# Power.net
KiCad netlist of a schematic drawn in Altium Designer
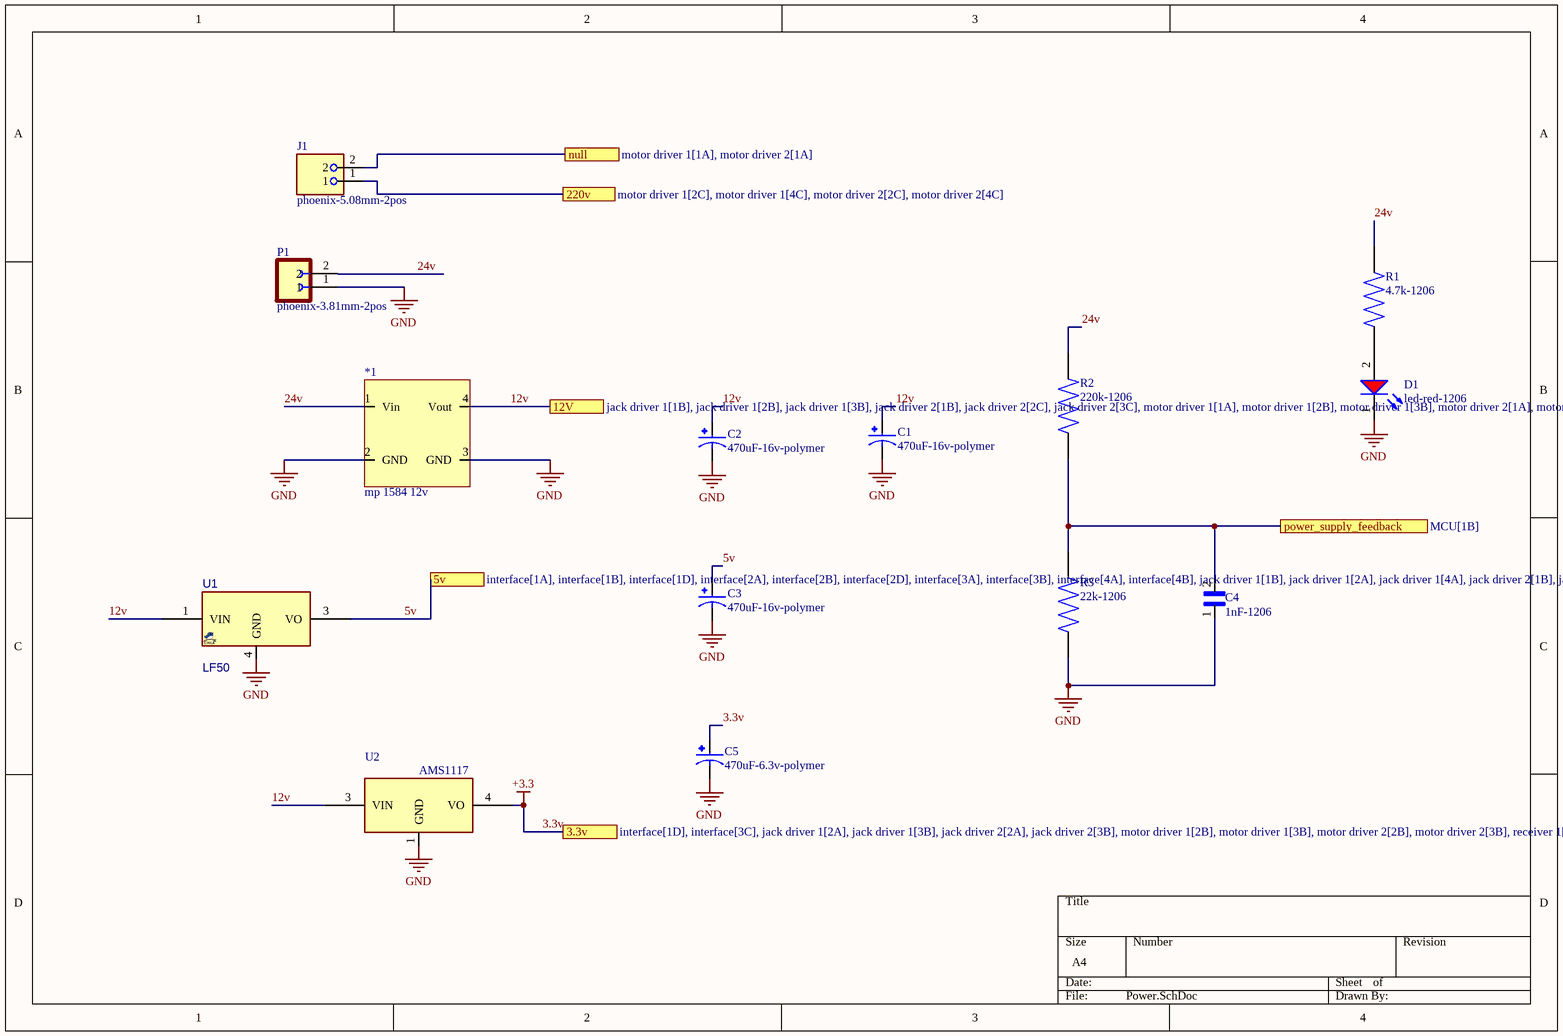
[diagram p0: Power.SchDoc]

(export (version "E")
  (design (tool "Eeschema 10.0.6"))
  (components
    (comp (ref "*1")
      (value "mp 1584 12v")
      (footprint "PCBComponent_1")
      (libsource (lib "mp1584 module") (part "Component_1"))
    )
    (comp (ref "C1")
      (value "470uF-16v-polymer")
      (footprint "CAP_EEEFN1H101L")
      (description "CAP ALUM 100UF 20% 50V SMD")
      (fields (field (name "MF") "Panasonic") (field (name "MP") "EEEFN1H101L"))
      (libsource (lib "100uF_50v") (part "EEEFN1H101L"))
    )
    (comp (ref "C2")
      (value "470uF-16v-polymer")
      (footprint "CAP_EEEFN1H101L")
      (description "CAP ALUM 100UF 20% 50V SMD")
      (fields (field (name "MF") "Panasonic") (field (name "MP") "EEEFN1H101L"))
      (libsource (lib "100uF_50v") (part "EEEFN1H101L"))
    )
    (comp (ref "C3")
      (value "470uF-16v-polymer")
      (footprint "CAP_EEEFN1H101L")
      (description "CAP ALUM 100UF 20% 50V SMD")
      (fields (field (name "MF") "Panasonic") (field (name "MP") "EEEFN1H101L"))
      (libsource (lib "100uF_50v") (part "EEEFN1H101L"))
    )
    (comp (ref "C4")
      (value "1nF-1206")
      (footprint "CAPC3216X180N")
      (description "1ÂµF Â±20% 50V Ceramic Capacitor X8R 1206 (3216 Metric)")
      (fields (field (name "MF") "TDK") (field (name "MP") "CGA5L3X8R1H105M160AB"))
      (libsource (lib "cap-1206") (part "CGA5L3X8R1H105M160AB"))
    )
    (comp (ref "C5")
      (value "470uF-6.3v-polymer")
      (footprint "CAP_EEEFN1H101L")
      (description "CAP ALUM 100UF 20% 50V SMD")
      (fields (field (name "MF") "Panasonic") (field (name "MP") "EEEFN1H101L"))
      (libsource (lib "100uF_50v") (part "EEEFN1H101L"))
    )
    (comp (ref "D1")
      (value "led-red-1206")
      (footprint "WL-SMRW_1206 dome_normal use")
      (description "WL-SMRW Mono-color Reverse mount Waterclear, SMT, size 1206 dome, Red, 2V, 20°")
      (fields
        (field (name "MANUFACTURER PART NUMBER") "156120RS82500")
        (field (name "MANUFACTURER") "Wurth Elektronik")
      )
      (libsource (lib "led-1206") (part "156120RS82500"))
    )
    (comp (ref "J1")
      (value "phoenix-5.08mm-2pos")
      (footprint "PHOENIX_1715721")
      (fields (field (name "MP") "1715721"))
      (libsource (lib "phoenix-2pos") (part "1715721"))
    )
    (comp (ref "P1")
      (value "phoenix-3.81mm-2pos")
      (footprint "PHOENIX_1803578")
      (description "2 Position Terminal Block Plug, Female Sockets 0.150 (3.81mm) 180Â° Free Hanging (In-Line)")
      (fields (field (name "MF") "Phoenix Contact") (field (name "MP") "1803578"))
      (libsource (lib "terminal-phoenix-3.81mm-2pos") (part "1803578"))
    )
    (comp (ref "R1")
      (value "4.7k-1206")
      (footprint "RESC3015X65N")
      (description "Res Thin Film 1206 10K Ohm 0.1% 1/8W Â±25ppm/Â°C Molded SMD SMD Paper T/R")
      (fields (field (name "MF") "TE Connectivity") (field (name "MP") "CPF1206B10KE1"))
      (libsource (lib "resistor-1206") (part "CPF1206B10KE1"))
    )
    (comp (ref "R2")
      (value "220k-1206")
      (footprint "RESC3015X65N")
      (description "Res Thin Film 1206 10K Ohm 0.1% 1/8W Â±25ppm/Â°C Molded SMD SMD Paper T/R")
      (fields (field (name "MF") "TE Connectivity") (field (name "MP") "CPF1206B10KE1"))
      (libsource (lib "resistor-1206") (part "CPF1206B10KE1"))
    )
    (comp (ref "R3")
      (value "22k-1206")
      (footprint "RESC3015X65N")
      (description "Res Thin Film 1206 10K Ohm 0.1% 1/8W Â±25ppm/Â°C Molded SMD SMD Paper T/R")
      (fields (field (name "MF") "TE Connectivity") (field (name "MP") "CPF1206B10KE1"))
      (libsource (lib "resistor-1206") (part "CPF1206B10KE1"))
    )
    (comp (ref "U1")
      (value "LF50")
      (footprint "DPAK_3")
      (description "REG, Linear, LDO0.45V, 0.5A, TO-252")
      (fields (field (name "MANF_P#") "LF33CDT") (field (name "MANF") "ST"))
      (libsource (lib "pwr_REG_linear") (part "VREG_LFXX_TO252"))
    )
    (comp (ref "U2")
      (value "AMS1117")
      (footprint "DPAK_3")
      (libsource (lib "pwr_REG_linear") (part "VREG_AMS1117_DPACK3"))
    )
  )
  (nets
    (net (code "1") (name "+3.3") (class "Default")
      (node (ref "C5") (pin "1") (pinfunction "1_1") (pintype "passive"))
      (node (ref "U2") (pin "4") (pinfunction "VO_4") (pintype "passive"))
    )
    (net (code "2") (name "/5v") (class "Default")
      (node (ref "C3") (pin "1") (pinfunction "1_1") (pintype "passive"))
      (node (ref "U1") (pin "3") (pinfunction "VO_3") (pintype "passive"))
    )
    (net (code "3") (name "/12v") (class "Default")
      (node (ref "*1") (pin "4") (pinfunction "Vout_4") (pintype "passive"))
      (node (ref "C1") (pin "1") (pinfunction "1_1") (pintype "passive"))
      (node (ref "C2") (pin "1") (pinfunction "1_1") (pintype "passive"))
      (node (ref "U1") (pin "1") (pinfunction "VIN_1") (pintype "passive"))
      (node (ref "U2") (pin "3") (pinfunction "VIN_3") (pintype "passive"))
    )
    (net (code "4") (name "/24v") (class "Default")
      (node (ref "*1") (pin "1") (pinfunction "Vin_1") (pintype "passive"))
      (node (ref "P1") (pin "2") (pinfunction "2_2") (pintype "passive"))
      (node (ref "R1") (pin "2") (pinfunction "2_2") (pintype "passive"))
      (node (ref "R2") (pin "2") (pinfunction "2_2") (pintype "passive"))
    )
    (net (code "5") (name "/220v") (class "Default")
      (node (ref "J1") (pin "1") (pinfunction "1_1") (pintype "passive"))
    )
    (net (code "6") (name "/null") (class "Default")
      (node (ref "J1") (pin "2") (pinfunction "2_2") (pintype "passive"))
    )
    (net (code "7") (name "/power_supply_feedback") (class "Default")
      (node (ref "C4") (pin "2") (pinfunction "2_2") (pintype "passive"))
      (node (ref "R2") (pin "1") (pinfunction "1_1") (pintype "passive"))
      (node (ref "R3") (pin "2") (pinfunction "2_2") (pintype "passive"))
    )
    (net (code "8") (name "GND") (class "Default")
      (node (ref "*1") (pin "2") (pinfunction "GND_2") (pintype "passive"))
      (node (ref "*1") (pin "3") (pinfunction "GND_3") (pintype "passive"))
      (node (ref "C1") (pin "2") (pinfunction "2_2") (pintype "passive"))
      (node (ref "C2") (pin "2") (pinfunction "2_2") (pintype "passive"))
      (node (ref "C3") (pin "2") (pinfunction "2_2") (pintype "passive"))
      (node (ref "C4") (pin "1") (pinfunction "1_1") (pintype "passive"))
      (node (ref "C5") (pin "2") (pinfunction "2_2") (pintype "passive"))
      (node (ref "D1") (pin "1") (pinfunction "K_1") (pintype "passive"))
      (node (ref "P1") (pin "1") (pinfunction "1_1") (pintype "passive"))
      (node (ref "R3") (pin "1") (pinfunction "1_1") (pintype "passive"))
      (node (ref "U1") (pin "4") (pinfunction "GND_4") (pintype "passive"))
      (node (ref "U2") (pin "1") (pinfunction "GND_1") (pintype "passive"))
    )
    (net (code "9") (name "Net-(D1-A)") (class "Default")
      (node (ref "D1") (pin "2") (pinfunction "A_2") (pintype "passive"))
      (node (ref "R1") (pin "1") (pinfunction "1_1") (pintype "passive"))
    )
  )
)
